# SerialConverter.net
KiCad netlist of a schematic drawn in Altium Designer
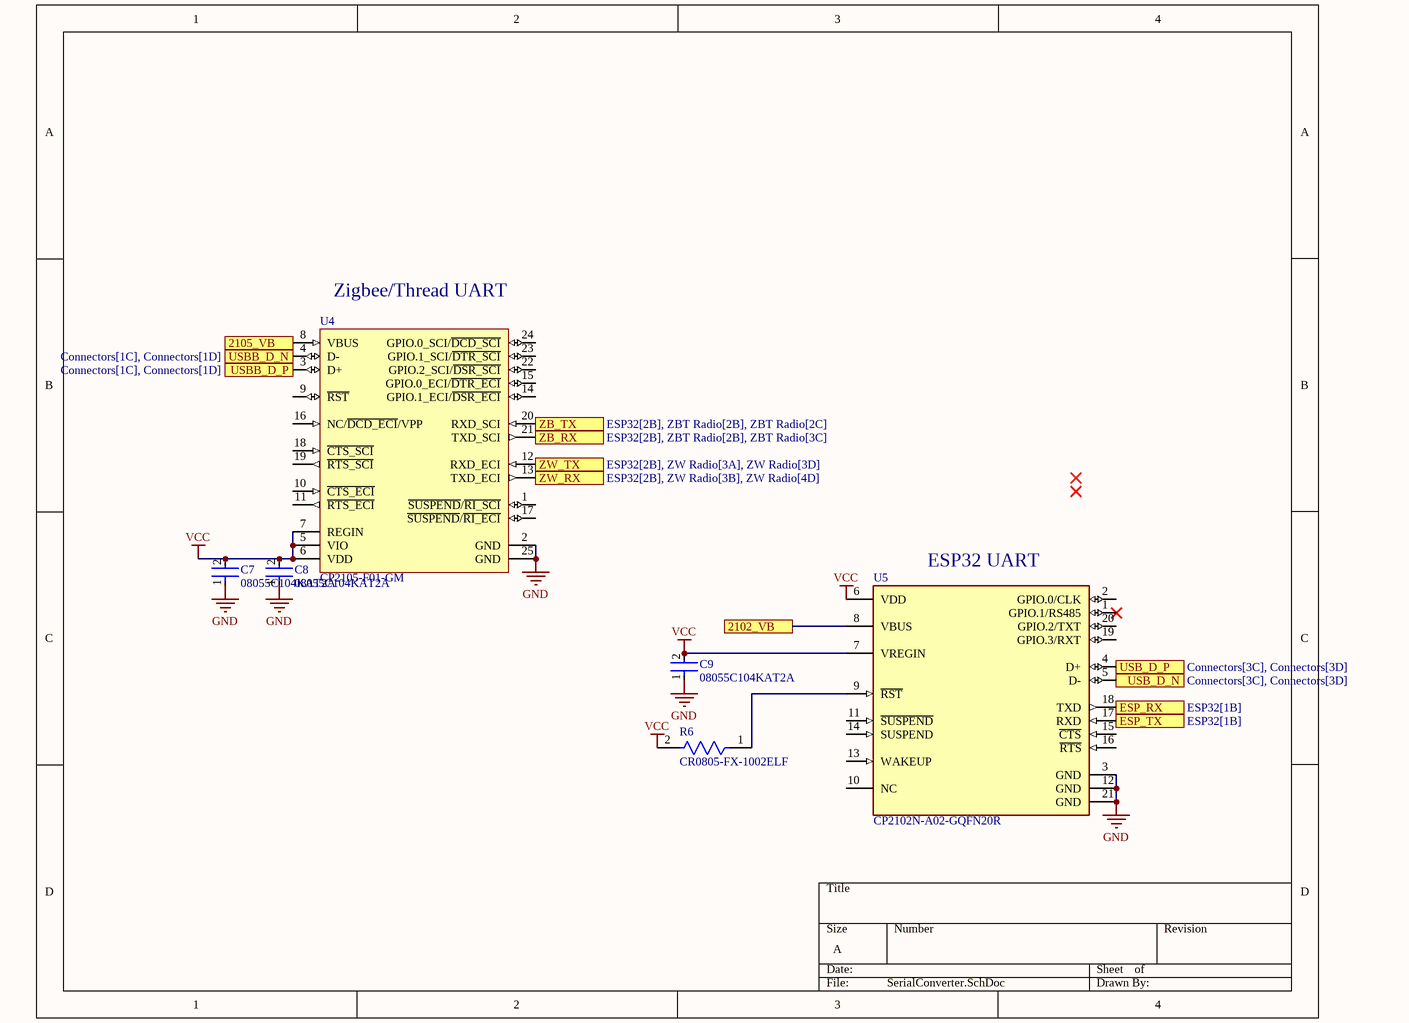
[diagram p0: SerialConverter.SchDoc]

(export (version "E")
  (design (tool "Eeschema 10.0.6"))
  (components
    (comp (ref "C7")
      (value "08055C104KAT2A")
      (footprint "FP-0805-L_2_01_0_2-W_1_25-IPC_C")
      (description "General Purpose Ceramic Capacitor, 0805, 100nF, 10%, X7R, 0.15, 50V")
      (fields (field (name "TOLERANCE") "10%") (field (name "VOLTAGE") "50V"))
      (libsource (lib "Altium Content Vault") (part "02cd4be3c70576c341d710602a673aa"))
    )
    (comp (ref "C8")
      (value "08055C104KAT2A")
      (footprint "FP-0805-L_2_01_0_2-W_1_25-IPC_C")
      (description "General Purpose Ceramic Capacitor, 0805, 100nF, 10%, X7R, 0.15, 50V")
      (fields (field (name "TOLERANCE") "10%") (field (name "VOLTAGE") "50V"))
      (libsource (lib "Altium Content Vault") (part "02cd4be3c70576c341d710602a673aa"))
    )
    (comp (ref "C9")
      (value "08055C104KAT2A")
      (footprint "FP-0805-L_2_01_0_2-W_1_25-IPC_C")
      (description "General Purpose Ceramic Capacitor, 0805, 100nF, 10%, X7R, 0.15, 50V")
      (fields (field (name "TOLERANCE") "10%") (field (name "VOLTAGE") "50V"))
      (libsource (lib "Altium Content Vault") (part "02cd4be3c70576c341d710602a673aa"))
    )
    (comp (ref "R6")
      (value "CR0805-FX-1002ELF")
      (footprint "FP-CR0805-IPC_A")
      (description "Thick Film Chip Resistors 0805 10kΩ 0.125W 1% 100ppm/°C")
      (fields (field (name "TOLERANCE") "1%"))
      (libsource (lib "Altium Content Vault") (part "1029c3af85768c4190bb7ad29bc67b5"))
    )
    (comp (ref "U4")
      (value "CP2105-F01-GM")
      (footprint "SLAB-QFN-24-2675x2675TP_N")
      (fields (field (name "MANUFACTURER") "Silicon Labs"))
      (libsource (lib "Altium Content Vault") (part "SLAB-CP2105-QFN-24-25"))
    )
    (comp (ref "U5")
      (value "CP2102N-A02-GQFN20R")
      (footprint "FP-CP2102N-A02-GQFN20R-MFG")
      (description "IC USB TO UART BRIDGE QFN20")
      (libsource (lib "Altium Content Vault") (part "12297b18919ed2bc2a0fed00377f037"))
    )
  )
  (nets
    (net (code "1") (name "/2102_VB") (class "Default")
      (node (ref "U5") (pin "8") (pinfunction "VBUS_8") (pintype "power_in"))
    )
    (net (code "2") (name "/2105_VB") (class "Default")
      (node (ref "U4") (pin "8") (pinfunction "VBUS_8") (pintype "input"))
    )
    (net (code "3") (name "/ESP_RX") (class "Default")
      (node (ref "U5") (pin "18") (pinfunction "TXD_18") (pintype "output"))
    )
    (net (code "4") (name "/ESP_TX") (class "Default")
      (node (ref "U5") (pin "17") (pinfunction "RXD_17") (pintype "input"))
    )
    (net (code "5") (name "/USBB_D_N") (class "Default")
      (node (ref "U4") (pin "4") (pinfunction "D-_4") (pintype "bidirectional"))
    )
    (net (code "6") (name "/USBB_D_P") (class "Default")
      (node (ref "U4") (pin "3") (pinfunction "D+_3") (pintype "bidirectional"))
    )
    (net (code "7") (name "/USB_D_N") (class "Default")
      (node (ref "U5") (pin "5") (pinfunction "D-_5") (pintype "bidirectional"))
    )
    (net (code "8") (name "/USB_D_P") (class "Default")
      (node (ref "U5") (pin "4") (pinfunction "D+_4") (pintype "bidirectional"))
    )
    (net (code "9") (name "/ZB_RX") (class "Default")
      (node (ref "U4") (pin "21") (pinfunction "TXD_SCI_21") (pintype "output"))
    )
    (net (code "10") (name "/ZB_TX") (class "Default")
      (node (ref "U4") (pin "20") (pinfunction "RXD_SCI_20") (pintype "input"))
    )
    (net (code "11") (name "/ZW_RX") (class "Default")
      (node (ref "U4") (pin "13") (pinfunction "TXD_ECI_13") (pintype "output"))
    )
    (net (code "12") (name "/ZW_TX") (class "Default")
      (node (ref "U4") (pin "12") (pinfunction "RXD_ECI_12") (pintype "input"))
    )
    (net (code "13") (name "GND") (class "Default")
      (node (ref "C7") (pin "1") (pinfunction "1_1") (pintype "passive"))
      (node (ref "C8") (pin "1") (pinfunction "1_1") (pintype "passive"))
      (node (ref "C9") (pin "1") (pinfunction "1_1") (pintype "passive"))
      (node (ref "U4") (pin "2") (pinfunction "GND_2") (pintype "power_in"))
      (node (ref "U4") (pin "25") (pinfunction "GND_25") (pintype "power_in"))
      (node (ref "U5") (pin "12") (pinfunction "GND_12") (pintype "power_in"))
      (node (ref "U5") (pin "21") (pinfunction "GND_21") (pintype "power_in"))
      (node (ref "U5") (pin "3") (pinfunction "GND_3") (pintype "power_in"))
    )
    (net (code "14") (name "Net-(U5-~{RST})") (class "Default")
      (node (ref "R6") (pin "1") (pinfunction "1_1") (pintype "passive"))
      (node (ref "U5") (pin "9") (pinfunction "~{RST}_9") (pintype "input"))
    )
    (net (code "15") (name "VCC") (class "Default")
      (node (ref "C7") (pin "2") (pinfunction "2_2") (pintype "passive"))
      (node (ref "C8") (pin "2") (pinfunction "2_2") (pintype "passive"))
      (node (ref "C9") (pin "2") (pinfunction "2_2") (pintype "passive"))
      (node (ref "R6") (pin "2") (pinfunction "2_2") (pintype "passive"))
      (node (ref "U4") (pin "5") (pinfunction "VIO_5") (pintype "power_in"))
      (node (ref "U4") (pin "6") (pinfunction "VDD_6") (pintype "power_in"))
      (node (ref "U4") (pin "7") (pinfunction "REGIN_7") (pintype "power_in"))
      (node (ref "U5") (pin "6") (pinfunction "VDD_6") (pintype "power_in"))
      (node (ref "U5") (pin "7") (pinfunction "VREGIN_7") (pintype "passive"))
    )
    (net (code "16") (name "unconnected-(U4-GPIO.0_ECI{slash}~{DTR_ECI}-Pad15)") (class "Default")
      (node (ref "U4") (pin "15") (pinfunction "GPIO.0_ECI/~{DTR_ECI}_15") (pintype "bidirectional"))
    )
    (net (code "17") (name "unconnected-(U4-GPIO.0_SCI{slash}~{DCD_SCI}-Pad24)") (class "Default")
      (node (ref "U4") (pin "24") (pinfunction "GPIO.0_SCI/~{DCD_SCI}_24") (pintype "bidirectional"))
    )
    (net (code "18") (name "unconnected-(U4-GPIO.1_ECI{slash}~{DSR_ECI}-Pad14)") (class "Default")
      (node (ref "U4") (pin "14") (pinfunction "GPIO.1_ECI/~{DSR_ECI}_14") (pintype "bidirectional"))
    )
    (net (code "19") (name "unconnected-(U4-GPIO.1_SCI{slash}~{DTR_SCI}-Pad23)") (class "Default")
      (node (ref "U4") (pin "23") (pinfunction "GPIO.1_SCI/~{DTR_SCI}_23") (pintype "bidirectional"))
    )
    (net (code "20") (name "unconnected-(U4-GPIO.2_SCI{slash}~{DSR_SCI}-Pad22)") (class "Default")
      (node (ref "U4") (pin "22") (pinfunction "GPIO.2_SCI/~{DSR_SCI}_22") (pintype "bidirectional"))
    )
    (net (code "21") (name "unconnected-(U4-NC{slash}~{DCD_ECI}{slash}VPP-Pad16)") (class "Default")
      (node (ref "U4") (pin "16") (pinfunction "NC/~{DCD_ECI}/VPP_16") (pintype "input"))
    )
    (net (code "22") (name "unconnected-(U4-~{CTS_ECI}-Pad10)") (class "Default")
      (node (ref "U4") (pin "10") (pinfunction "~{CTS_ECI}_10") (pintype "input"))
    )
    (net (code "23") (name "unconnected-(U4-~{CTS_SCI}-Pad18)") (class "Default")
      (node (ref "U4") (pin "18") (pinfunction "~{CTS_SCI}_18") (pintype "input"))
    )
    (net (code "24") (name "unconnected-(U4-~{RST}-Pad9)") (class "Default")
      (node (ref "U4") (pin "9") (pinfunction "~{RST}_9") (pintype "bidirectional"))
    )
    (net (code "25") (name "unconnected-(U4-~{RTS_ECI}-Pad11)") (class "Default")
      (node (ref "U4") (pin "11") (pinfunction "~{RTS_ECI}_11") (pintype "output"))
    )
    (net (code "26") (name "unconnected-(U4-~{RTS_SCI}-Pad19)") (class "Default")
      (node (ref "U4") (pin "19") (pinfunction "~{RTS_SCI}_19") (pintype "output"))
    )
    (net (code "27") (name "unconnected-(U4-~{SUSPEND}{slash}~{RI_ECI}-Pad17)") (class "Default")
      (node (ref "U4") (pin "17") (pinfunction "~{SUSPEND}/~{RI_ECI}_17") (pintype "bidirectional"))
    )
    (net (code "28") (name "unconnected-(U4-~{SUSPEND}{slash}~{RI_SCI}-Pad1)") (class "Default")
      (node (ref "U4") (pin "1") (pinfunction "~{SUSPEND}/~{RI_SCI}_1") (pintype "bidirectional"))
    )
    (net (code "29") (name "unconnected-(U5-GPIO.0{slash}CLK-Pad2)") (class "Default")
      (node (ref "U5") (pin "2") (pinfunction "GPIO.0/CLK_2") (pintype "bidirectional"))
    )
    (net (code "30") (name "unconnected-(U5-GPIO.1{slash}RS485-Pad1)") (class "Default")
      (node (ref "U5") (pin "1") (pinfunction "GPIO.1/RS485_1") (pintype "bidirectional+no_connect"))
    )
    (net (code "31") (name "unconnected-(U5-GPIO.2{slash}TXT-Pad20)") (class "Default")
      (node (ref "U5") (pin "20") (pinfunction "GPIO.2/TXT_20") (pintype "bidirectional"))
    )
    (net (code "32") (name "unconnected-(U5-GPIO.3{slash}RXT-Pad19)") (class "Default")
      (node (ref "U5") (pin "19") (pinfunction "GPIO.3/RXT_19") (pintype "bidirectional"))
    )
    (net (code "33") (name "unconnected-(U5-NC-Pad10)") (class "Default")
      (node (ref "U5") (pin "10") (pinfunction "NC_10") (pintype "passive"))
    )
    (net (code "34") (name "unconnected-(U5-SUSPEND-Pad14)") (class "Default")
      (node (ref "U5") (pin "14") (pinfunction "SUSPEND_14") (pintype "input"))
    )
    (net (code "35") (name "unconnected-(U5-WAKEUP-Pad13)") (class "Default")
      (node (ref "U5") (pin "13") (pinfunction "WAKEUP_13") (pintype "input"))
    )
    (net (code "36") (name "unconnected-(U5-~{CTS}-Pad15)") (class "Default")
      (node (ref "U5") (pin "15") (pinfunction "~{CTS}_15") (pintype "input"))
    )
    (net (code "37") (name "unconnected-(U5-~{RTS}-Pad16)") (class "Default")
      (node (ref "U5") (pin "16") (pinfunction "~{RTS}_16") (pintype "input"))
    )
    (net (code "38") (name "unconnected-(U5-~{SUSPEND}-Pad11)") (class "Default")
      (node (ref "U5") (pin "11") (pinfunction "~{SUSPEND}_11") (pintype "input"))
    )
  )
)
